# SD_CARD.net
KiCad netlist of a schematic drawn in Altium Designer
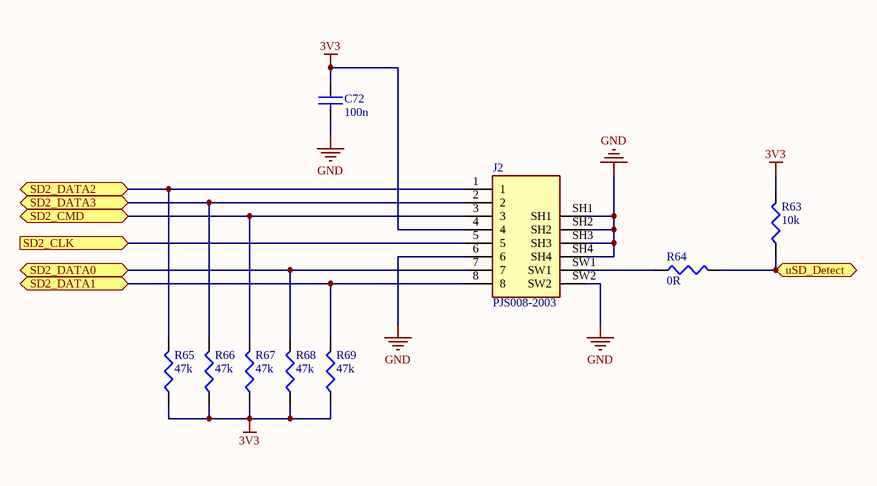
[diagram p0: SD_CARD.SchDoc]

(export (version "E")
  (design (tool "Eeschema 10.0.6"))
  (components
    (comp (ref "C72")
      (value "100n")
      (footprint "C0402")
      (description "CAP CER .10UF 50V X5R 10% 0402")
      (fields
        (field (name "MANUFACTURER") "TDK Corporation")
        (field (name "MANUFACTURER PART NUMBER") "C1005X5R1H104K")
      )
      (libsource (lib "iMX6_Rex_Development_Baseboard_V1I1") (part "C1005X5R1H104K"))
    )
    (comp (ref "J2")
      (value "PJS008-2003")
      (footprint "PJS008-2003-noHole")
      (description "Connector")
      (fields
        (field (name "MANUFACTURER_PART_NUMBER") "PJS008-2003-1")
        (field (name "MOUSER PART NUMBER") "945-PJS008-2003-1")
      )
      (libsource (lib "PJS008-2003") (part "PJS008-2003_noHole"))
    )
    (comp (ref "R63")
      (value "10k")
      (footprint "R0402")
      (description "RES 10.0K OHM 1/16W 1% 0402 SMD")
      (fields
        (field (name "MANUFACTURER") "Yageo")
        (field (name "MANUFACTURER PART NUMBER") "RC0402FR-0710KL")
      )
      (libsource (lib "iMX6_Rex_Development_Baseboard_V1I1") (part "RC0402FR-0710KL"))
    )
    (comp (ref "R64")
      (value "0R")
      (footprint "R0402")
      (description "RES 330 OHM 1/16W 1% 0402 SMD")
      (fields
        (field (name "MANUFACTURER") "Vishay Dale")
        (field (name "MANUFACTURER PART NUMBER") "CRCW0402330RFKED")
        (field (name ".CHECKED PCB") "RF")
        (field (name ".CHECKED SCH") "RF")
      )
      (libsource (lib "iMX6_Rex_Development_Baseboard_V1I1") (part "CRCW0402330RFKED"))
    )
    (comp (ref "R65")
      (value "47k")
      (footprint "R0402")
      (description "RES 10.0K OHM 1/16W 1% 0402 SMD")
      (fields
        (field (name "MANUFACTURER") "Yageo")
        (field (name "MANUFACTURER PART NUMBER") "RC0402FR-0710KL")
      )
      (libsource (lib "iMX6_Rex_Development_Baseboard_V1I1") (part "RC0402FR-0710KL"))
    )
    (comp (ref "R66")
      (value "47k")
      (footprint "R0402")
      (description "RES 10.0K OHM 1/16W 1% 0402 SMD")
      (fields
        (field (name "MANUFACTURER") "Yageo")
        (field (name "MANUFACTURER PART NUMBER") "RC0402FR-0710KL")
      )
      (libsource (lib "iMX6_Rex_Development_Baseboard_V1I1") (part "RC0402FR-0710KL"))
    )
    (comp (ref "R67")
      (value "47k")
      (footprint "R0402")
      (description "RES 10.0K OHM 1/16W 1% 0402 SMD")
      (fields
        (field (name "MANUFACTURER") "Yageo")
        (field (name "MANUFACTURER PART NUMBER") "RC0402FR-0710KL")
      )
      (libsource (lib "iMX6_Rex_Development_Baseboard_V1I1") (part "RC0402FR-0710KL"))
    )
    (comp (ref "R68")
      (value "47k")
      (footprint "R0402")
      (description "RES 10.0K OHM 1/16W 1% 0402 SMD")
      (fields
        (field (name "MANUFACTURER") "Yageo")
        (field (name "MANUFACTURER PART NUMBER") "RC0402FR-0710KL")
      )
      (libsource (lib "iMX6_Rex_Development_Baseboard_V1I1") (part "RC0402FR-0710KL"))
    )
    (comp (ref "R69")
      (value "47k")
      (footprint "R0402")
      (description "RES 10.0K OHM 1/16W 1% 0402 SMD")
      (fields
        (field (name "MANUFACTURER") "Yageo")
        (field (name "MANUFACTURER PART NUMBER") "RC0402FR-0710KL")
      )
      (libsource (lib "iMX6_Rex_Development_Baseboard_V1I1") (part "RC0402FR-0710KL"))
    )
  )
  (nets
    (net (code "1") (name "/SD2_CLK") (class "Default")
      (node (ref "J2") (pin "5") (pinfunction "5_5") (pintype "passive"))
    )
    (net (code "2") (name "/SD2_CMD") (class "Default")
      (node (ref "J2") (pin "3") (pinfunction "3_3") (pintype "passive"))
      (node (ref "R67") (pin "2") (pinfunction "2_2") (pintype "passive"))
    )
    (net (code "3") (name "/SD2_DATA0") (class "Default")
      (node (ref "J2") (pin "7") (pinfunction "7_7") (pintype "passive"))
      (node (ref "R68") (pin "2") (pinfunction "2_2") (pintype "passive"))
    )
    (net (code "4") (name "/SD2_DATA1") (class "Default")
      (node (ref "J2") (pin "8") (pinfunction "8_8") (pintype "passive"))
      (node (ref "R69") (pin "2") (pinfunction "2_2") (pintype "passive"))
    )
    (net (code "5") (name "/SD2_DATA2") (class "Default")
      (node (ref "J2") (pin "1") (pinfunction "1_1") (pintype "passive"))
      (node (ref "R65") (pin "2") (pinfunction "2_2") (pintype "passive"))
    )
    (net (code "6") (name "/SD2_DATA3") (class "Default")
      (node (ref "J2") (pin "2") (pinfunction "2_2") (pintype "passive"))
      (node (ref "R66") (pin "2") (pinfunction "2_2") (pintype "passive"))
    )
    (net (code "7") (name "/uSD_Detect") (class "Default")
      (node (ref "R63") (pin "1") (pinfunction "1_1") (pintype "passive"))
      (node (ref "R64") (pin "2") (pinfunction "2_2") (pintype "passive"))
    )
    (net (code "8") (name "3V3") (class "Default")
      (node (ref "C72") (pin "1") (pinfunction "1_1") (pintype "passive"))
      (node (ref "J2") (pin "4") (pinfunction "4_4") (pintype "passive"))
      (node (ref "R63") (pin "2") (pinfunction "2_2") (pintype "passive"))
      (node (ref "R65") (pin "1") (pinfunction "1_1") (pintype "passive"))
      (node (ref "R66") (pin "1") (pinfunction "1_1") (pintype "passive"))
      (node (ref "R67") (pin "1") (pinfunction "1_1") (pintype "passive"))
      (node (ref "R68") (pin "1") (pinfunction "1_1") (pintype "passive"))
      (node (ref "R69") (pin "1") (pinfunction "1_1") (pintype "passive"))
    )
    (net (code "9") (name "GND") (class "Default")
      (node (ref "C72") (pin "2") (pinfunction "2_2") (pintype "passive"))
      (node (ref "J2") (pin "6") (pinfunction "6_6") (pintype "passive"))
      (node (ref "J2") (pin "SH1") (pinfunction "SH1_SH1") (pintype "passive"))
      (node (ref "J2") (pin "SH2") (pinfunction "SH2_SH2") (pintype "passive"))
      (node (ref "J2") (pin "SH3") (pinfunction "SH3_SH3") (pintype "passive"))
      (node (ref "J2") (pin "SH4") (pinfunction "SH4_SH4") (pintype "passive"))
      (node (ref "J2") (pin "SW2") (pinfunction "SW2_SW2") (pintype "passive"))
    )
    (net (code "10") (name "Net-(J2-PadSW1)") (class "Default")
      (node (ref "J2") (pin "SW1") (pinfunction "SW1_SW1") (pintype "passive"))
      (node (ref "R64") (pin "1") (pinfunction "1_1") (pintype "passive"))
    )
  )
)
